# Amp2.net
KiCad netlist of a schematic drawn in EasyEDA
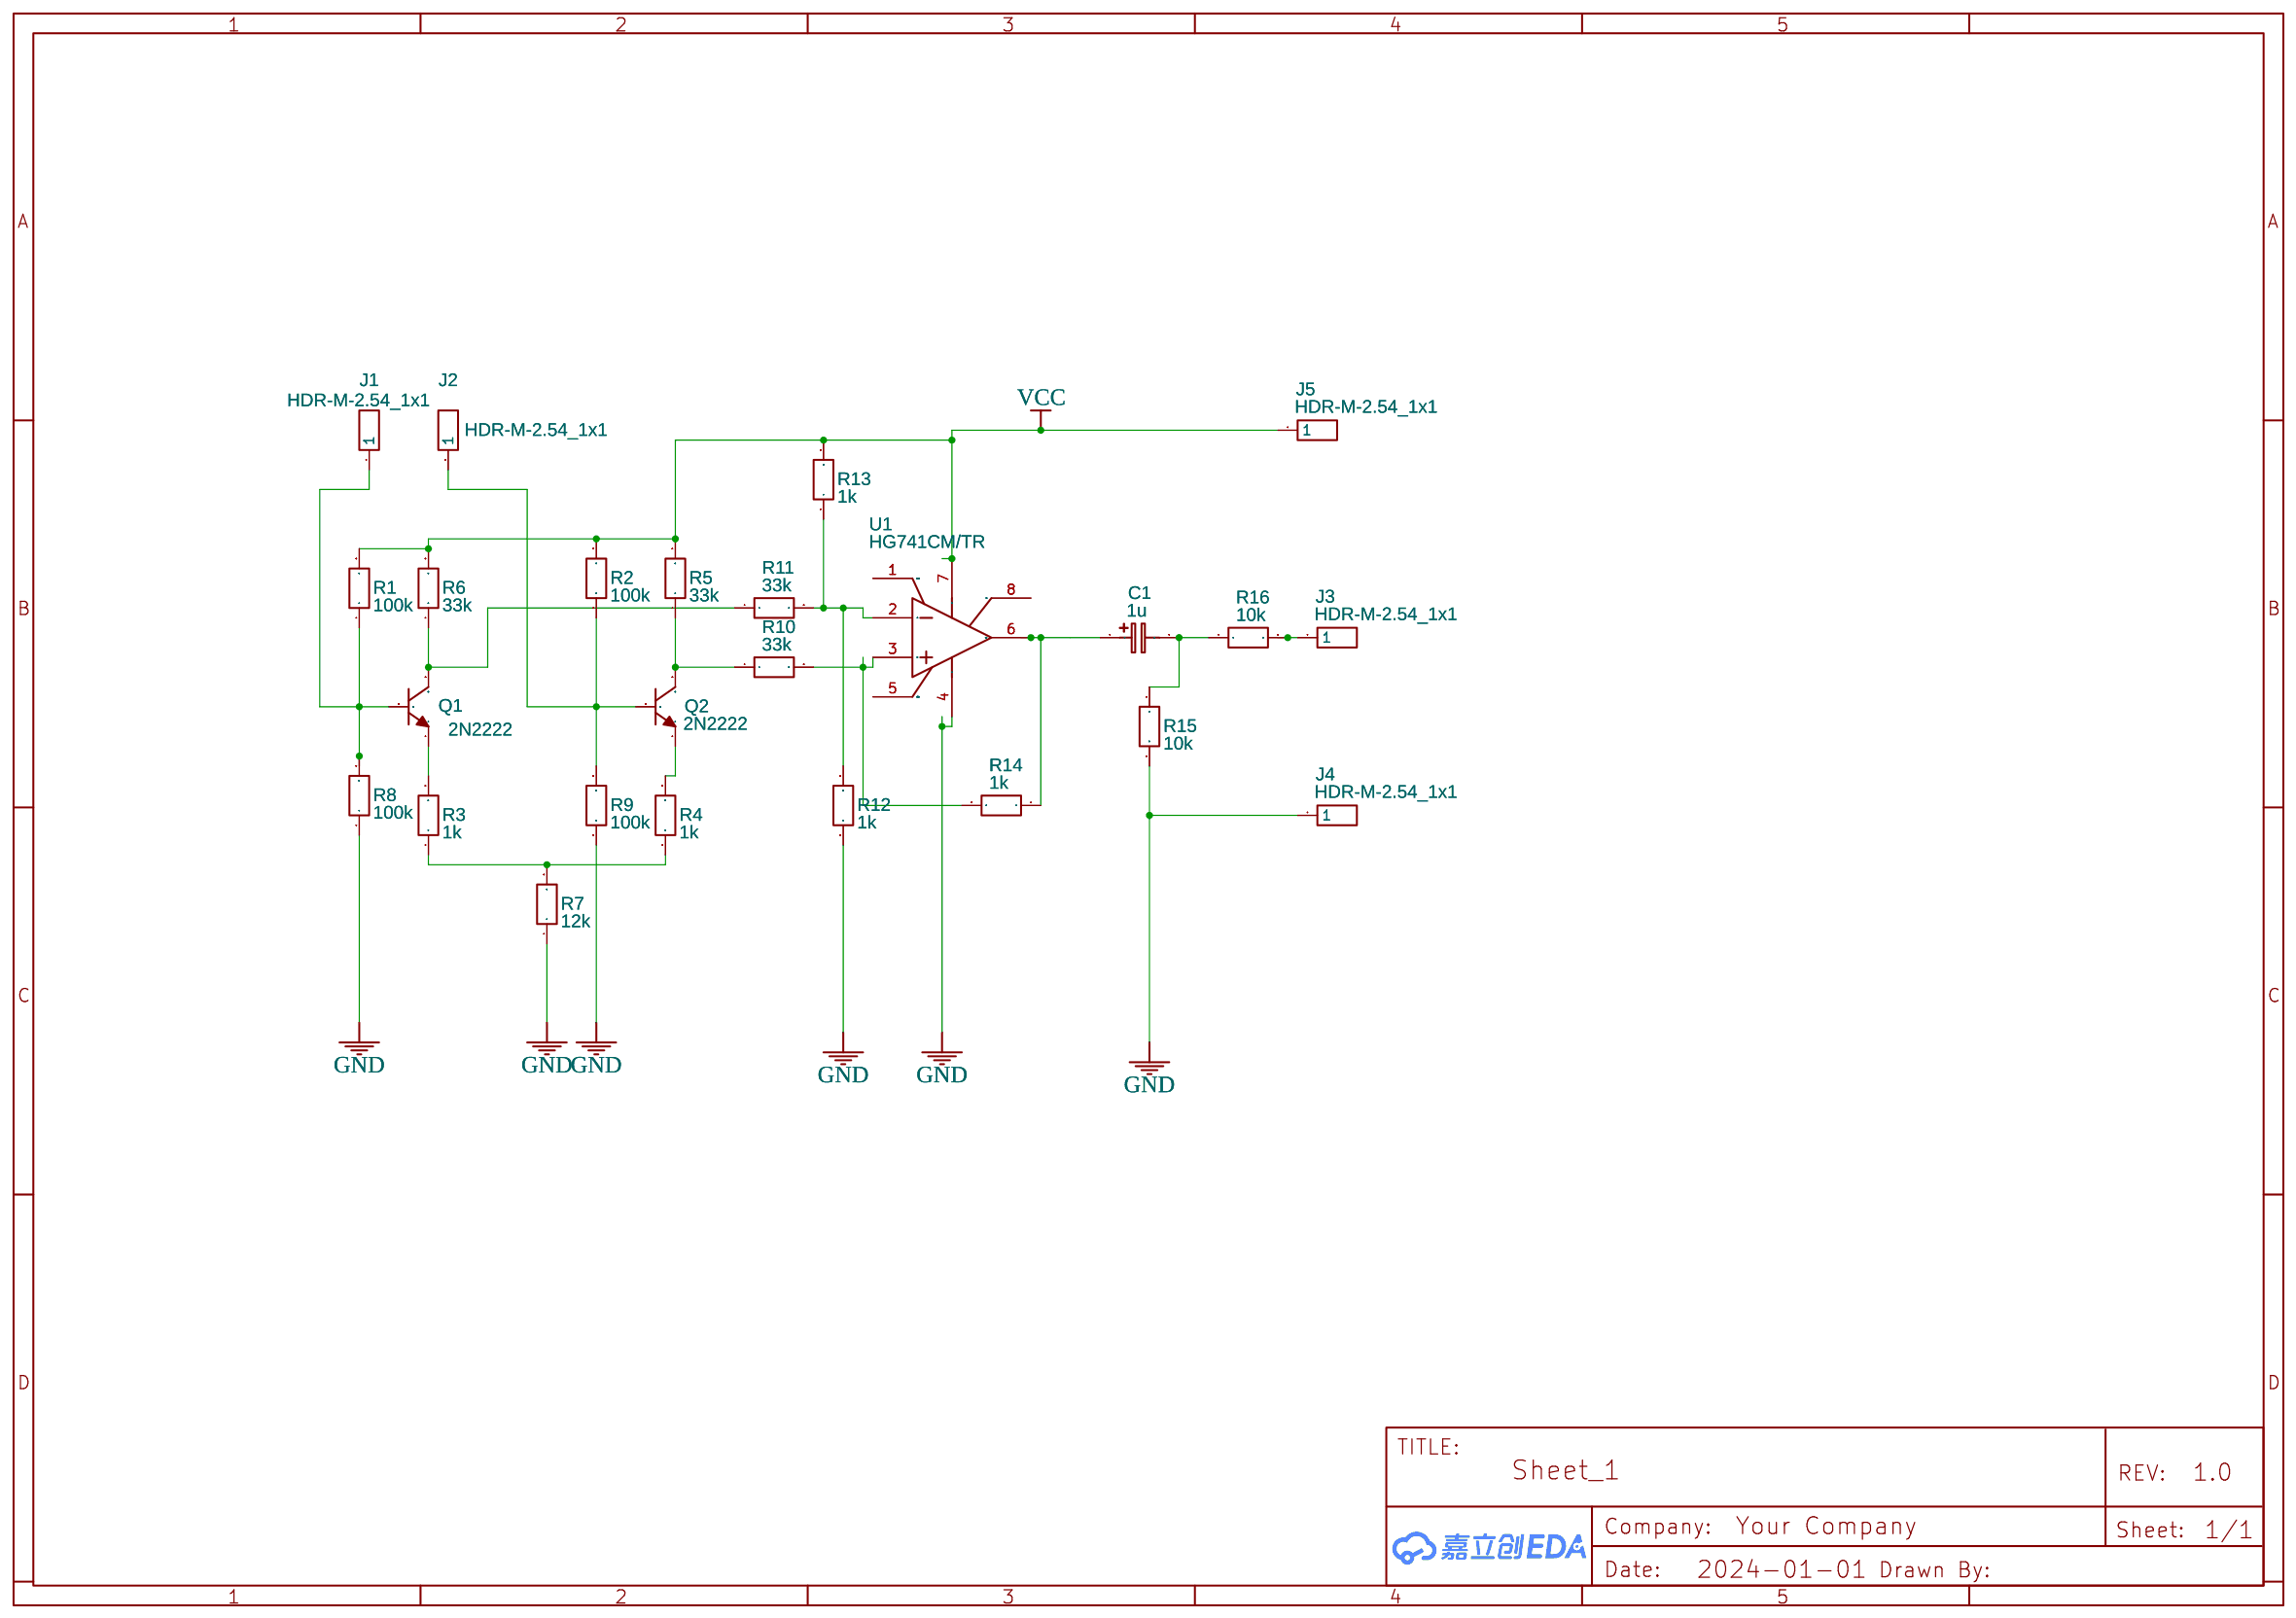
[diagram p0: schematic sheet]

(export (version "E")
  (design (tool "Eeschema 10.0.6"))
  (components
    (comp (ref "C1") (value "1u") (libsource (lib "") (part "C_Tan_SMD_A_EU")))
    (comp (ref "J1")
      (value "HDR-M-2.54_1x1")
      (fields (field (name "BOM_Supplier Part") "C81276"))
      (libsource (lib "") (part "HDR-M-2.54_1x1"))
    )
    (comp (ref "J2")
      (value "HDR-M-2.54_1x1")
      (fields (field (name "BOM_Supplier Part") "C81276"))
      (libsource (lib "") (part "HDR-M-2.54_1x1"))
    )
    (comp (ref "J3")
      (value "HDR-M-2.54_1x1")
      (fields (field (name "BOM_Supplier Part") "C81276"))
      (libsource (lib "") (part "HDR-M-2.54_1x1_1"))
    )
    (comp (ref "J4")
      (value "HDR-M-2.54_1x1")
      (fields (field (name "BOM_Supplier Part") "C81276"))
      (libsource (lib "") (part "HDR-M-2.54_1x1_1"))
    )
    (comp (ref "J5")
      (value "HDR-M-2.54_1x1")
      (fields (field (name "BOM_Supplier Part") "C81276"))
      (libsource (lib "") (part "HDR-M-2.54_1x1_1"))
    )
    (comp (ref "Q1")
      (value "2N2222")
      (fields
        (field (name "BOM_Manufacturer Part") "2n3904S-RTK/PS")
        (field (name "BOM_Supplier Part") "C18536")
      )
      (libsource (lib "") (part "2N3904(SOT-23)"))
    )
    (comp (ref "Q2")
      (value "2N2222")
      (fields
        (field (name "BOM_Manufacturer Part") "2n3904S-RTK/PS")
        (field (name "BOM_Supplier Part") "C18536")
      )
      (libsource (lib "") (part "2N3904(SOT-23)"))
    )
    (comp (ref "R1") (value "100k") (libsource (lib "") (part "R_0603_EU")))
    (comp (ref "R2") (value "100k") (libsource (lib "") (part "R_0603_EU")))
    (comp (ref "R3") (value "1k") (libsource (lib "") (part "R_0603_EU")))
    (comp (ref "R4") (value "1k") (libsource (lib "") (part "R_0603_EU")))
    (comp (ref "R5") (value "33k") (libsource (lib "") (part "R_0603_EU")))
    (comp (ref "R6") (value "33k") (libsource (lib "") (part "R_0603_EU")))
    (comp (ref "R7") (value "12k") (libsource (lib "") (part "R_0603_EU")))
    (comp (ref "R8") (value "100k") (libsource (lib "") (part "R_0603_EU")))
    (comp (ref "R9") (value "100k") (libsource (lib "") (part "R_0603_EU")))
    (comp (ref "R10") (value "33k") (libsource (lib "") (part "R_0603_EU_1")))
    (comp (ref "R11") (value "33k") (libsource (lib "") (part "R_0603_EU_1")))
    (comp (ref "R12") (value "1k") (libsource (lib "") (part "R_0603_EU")))
    (comp (ref "R13") (value "1k") (libsource (lib "") (part "R_0603_EU")))
    (comp (ref "R14") (value "1k") (libsource (lib "") (part "R_0603_EU_2")))
    (comp (ref "R15") (value "10k") (libsource (lib "") (part "R_0603_EU_3")))
    (comp (ref "R16") (value "10k") (libsource (lib "") (part "R_0603_EU_1")))
    (comp (ref "U1")
      (value "HG741CM/TR")
      (fields (field (name "Manufacturer") "HGSEMI(华冠)"))
      (libsource (lib "") (part "HG741CM/TR"))
    )
  )
  (nets
    (net (code "1") (name "GND") (class "Default")
      (node (ref "J4") (pin "1") (pinfunction "1_1") (pintype "input"))
      (node (ref "R12") (pin "1") (pinfunction "1_1") (pintype "unspecified"))
      (node (ref "R15") (pin "2") (pinfunction "2_2") (pintype "unspecified"))
      (node (ref "R7") (pin "1") (pinfunction "1_1") (pintype "unspecified"))
      (node (ref "R8") (pin "1") (pinfunction "1_1") (pintype "unspecified"))
      (node (ref "R9") (pin "1") (pinfunction "1_1") (pintype "unspecified"))
      (node (ref "U1") (pin "4") (pinfunction "V-_4") (pintype "passive"))
    )
    (net (code "2") (name "Net-(C1-Pad2)") (class "Default")
      (node (ref "C1") (pin "2") (pinfunction "2_2") (pintype "unspecified"))
      (node (ref "R15") (pin "1") (pinfunction "1_1") (pintype "unspecified"))
      (node (ref "R16") (pin "1") (pinfunction "1_1") (pintype "unspecified"))
    )
    (net (code "3") (name "Net-(J3-Pad1)") (class "Default")
      (node (ref "J3") (pin "1") (pinfunction "1_1") (pintype "input"))
      (node (ref "R16") (pin "2") (pinfunction "2_2") (pintype "unspecified"))
    )
    (net (code "4") (name "Net-(Q1-B)") (class "Default")
      (node (ref "J1") (pin "1") (pinfunction "1_1") (pintype "input"))
      (node (ref "Q1") (pin "2") (pinfunction "B_2") (pintype "input"))
      (node (ref "R1") (pin "1") (pinfunction "1_1") (pintype "unspecified"))
      (node (ref "R8") (pin "2") (pinfunction "2_2") (pintype "unspecified"))
    )
    (net (code "5") (name "Net-(Q1-C)") (class "Default")
      (node (ref "Q1") (pin "3") (pinfunction "C_3") (pintype "input"))
      (node (ref "R11") (pin "1") (pinfunction "1_1") (pintype "unspecified"))
      (node (ref "R6") (pin "1") (pinfunction "1_1") (pintype "unspecified"))
    )
    (net (code "6") (name "Net-(Q1-E)") (class "Default")
      (node (ref "Q1") (pin "1") (pinfunction "E_1") (pintype "input"))
      (node (ref "R3") (pin "2") (pinfunction "2_2") (pintype "unspecified"))
    )
    (net (code "7") (name "Net-(Q2-B)") (class "Default")
      (node (ref "J2") (pin "1") (pinfunction "1_1") (pintype "input"))
      (node (ref "Q2") (pin "2") (pinfunction "B_2") (pintype "input"))
      (node (ref "R2") (pin "1") (pinfunction "1_1") (pintype "unspecified"))
      (node (ref "R9") (pin "2") (pinfunction "2_2") (pintype "unspecified"))
    )
    (net (code "8") (name "Net-(Q2-C)") (class "Default")
      (node (ref "Q2") (pin "3") (pinfunction "C_3") (pintype "input"))
      (node (ref "R10") (pin "1") (pinfunction "1_1") (pintype "unspecified"))
      (node (ref "R5") (pin "1") (pinfunction "1_1") (pintype "unspecified"))
    )
    (net (code "9") (name "Net-(Q2-E)") (class "Default")
      (node (ref "Q2") (pin "1") (pinfunction "E_1") (pintype "input"))
      (node (ref "R4") (pin "2") (pinfunction "2_2") (pintype "unspecified"))
    )
    (net (code "10") (name "Net-(R3-Pad1)") (class "Default")
      (node (ref "R3") (pin "1") (pinfunction "1_1") (pintype "unspecified"))
      (node (ref "R4") (pin "1") (pinfunction "1_1") (pintype "unspecified"))
      (node (ref "R7") (pin "2") (pinfunction "2_2") (pintype "unspecified"))
    )
    (net (code "11") (name "Net-(U1-+IN)") (class "Default")
      (node (ref "R10") (pin "2") (pinfunction "2_2") (pintype "unspecified"))
      (node (ref "R14") (pin "2") (pinfunction "2_2") (pintype "unspecified"))
      (node (ref "U1") (pin "3") (pinfunction "+IN_3") (pintype "unspecified"))
    )
    (net (code "12") (name "Net-(U1--IN)") (class "Default")
      (node (ref "R11") (pin "2") (pinfunction "2_2") (pintype "unspecified"))
      (node (ref "R12") (pin "2") (pinfunction "2_2") (pintype "unspecified"))
      (node (ref "R13") (pin "1") (pinfunction "1_1") (pintype "unspecified"))
      (node (ref "U1") (pin "2") (pinfunction "-IN_2") (pintype "unspecified"))
    )
    (net (code "13") (name "Net-(U1-OUTPUT)") (class "Default")
      (node (ref "C1") (pin "1") (pinfunction "1_1") (pintype "unspecified"))
      (node (ref "R14") (pin "1") (pinfunction "1_1") (pintype "unspecified"))
      (node (ref "U1") (pin "6") (pinfunction "OUTPUT_6") (pintype "unspecified"))
    )
    (net (code "14") (name "VCC") (class "Default")
      (node (ref "J5") (pin "1") (pinfunction "1_1") (pintype "input"))
      (node (ref "R1") (pin "2") (pinfunction "2_2") (pintype "unspecified"))
      (node (ref "R13") (pin "2") (pinfunction "2_2") (pintype "unspecified"))
      (node (ref "R2") (pin "2") (pinfunction "2_2") (pintype "unspecified"))
      (node (ref "R5") (pin "2") (pinfunction "2_2") (pintype "unspecified"))
      (node (ref "R6") (pin "2") (pinfunction "2_2") (pintype "unspecified"))
      (node (ref "U1") (pin "7") (pinfunction "V+_7") (pintype "passive"))
    )
    (net (code "15") (name "unconnected-(U1-NC-Pad8)") (class "Default")
      (node (ref "U1") (pin "8") (pinfunction "NC_8") (pintype "unspecified"))
    )
    (net (code "16") (name "unconnected-(U1-OFFSET_NULL-Pad1)") (class "Default")
      (node (ref "U1") (pin "1") (pinfunction "OFFSET_NULL_1") (pintype "unspecified"))
    )
    (net (code "17") (name "unconnected-(U1-OFFSET_NULL-Pad5)") (class "Default")
      (node (ref "U1") (pin "5") (pinfunction "OFFSET_NULL_5") (pintype "unspecified"))
    )
  )
)
